# UPCNSL-ABS-PVC-BOT.net
KiCad netlist of a schematic drawn in Altium Designer
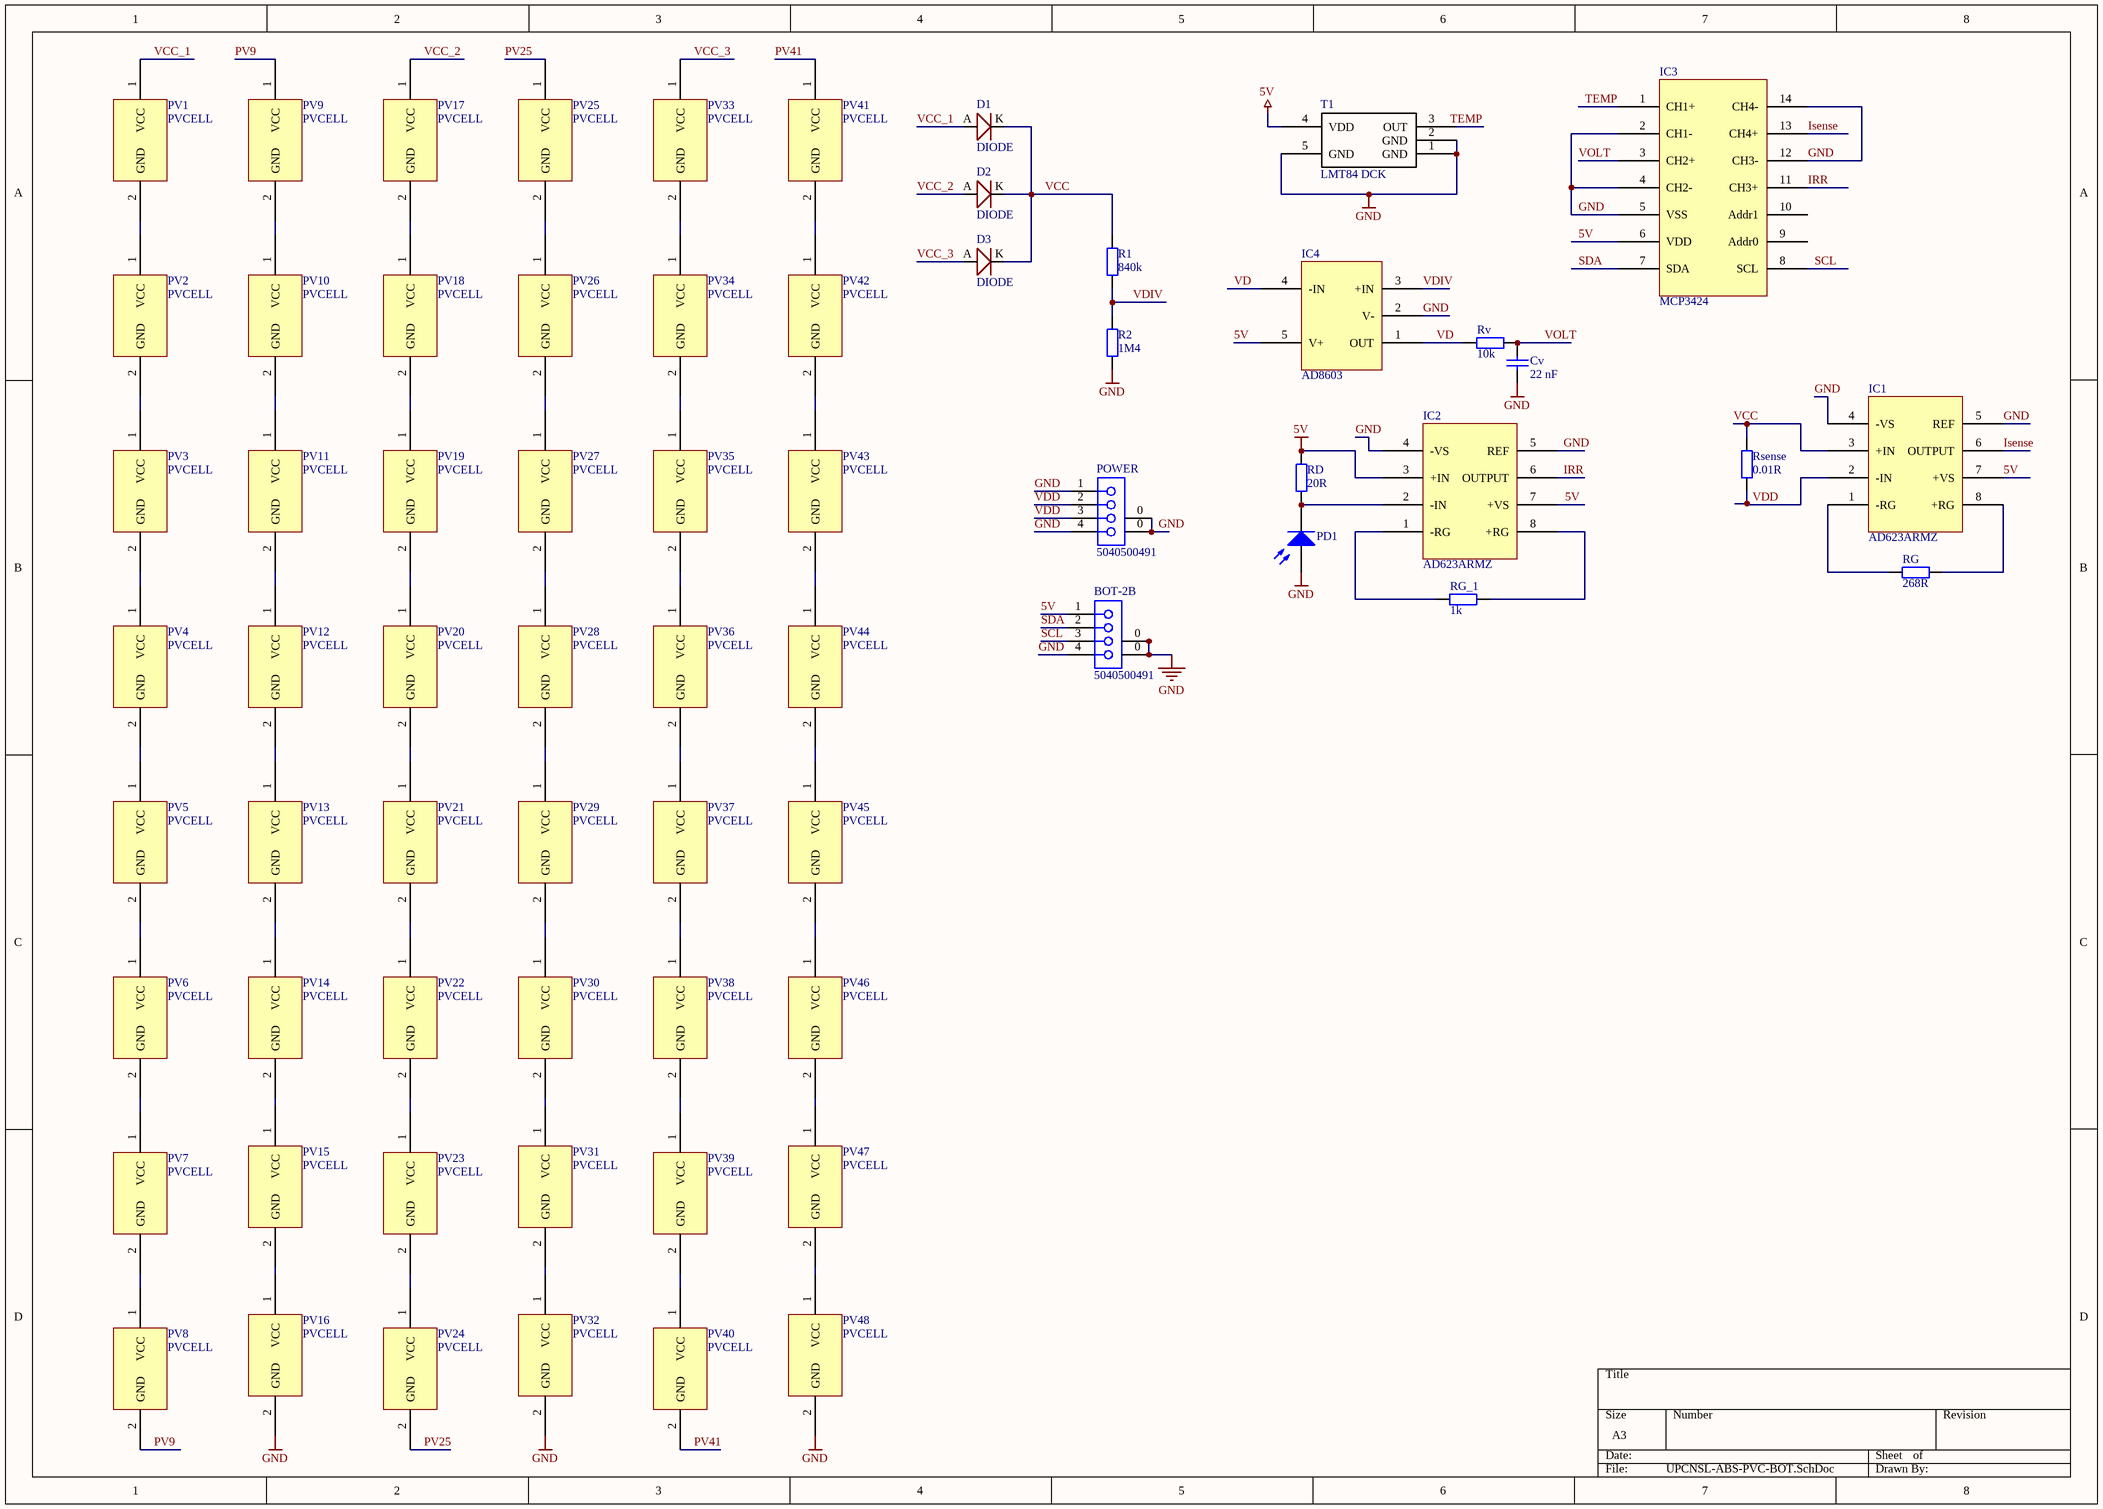
[diagram p0: UPCNSL-ABS-PVC-BOT.SchDoc]

(export (version "E")
  (design (tool "Eeschema 10.0.6"))
  (components
    (comp (ref "BOT-2B")
      (value "5040500491")
      (footprint "5040500491")
      (libsource (lib "3CAT_Connectors") (part "MOLEX_5040500491"))
    )
    (comp (ref "Cv")
      (value "22 nF")
      (footprint "CAP0603")
      (description "Capacitor")
      (fields (field (name "Comment") "CAP0603"))
      (libsource (lib "UPCNSL-ABS-FLS-ARD_v1.2") (part "CAP0603"))
    )
    (comp (ref "D1")
      (value "DIODE")
      (footprint "(Schottky diode) SODFL160X70-2N")
      (libsource (lib "UPCNSL-ABS-FLS-ARD_v1.2") (part "DIODE"))
    )
    (comp (ref "D2")
      (value "DIODE")
      (footprint "(Schottky diode) SODFL160X70-2N")
      (libsource (lib "UPCNSL-ABS-FLS-ARD_v1.2") (part "DIODE"))
    )
    (comp (ref "D3")
      (value "DIODE")
      (footprint "(Schottky diode) SODFL160X70-2N")
      (libsource (lib "UPCNSL-ABS-FLS-ARD_v1.2") (part "DIODE"))
    )
    (comp (ref "IC1")
      (value "AD623ARMZ")
      (footprint "AD623ARMZ")
      (libsource (lib "UPCNSL-ABS-FLS-PVC") (part "AD623ARMZ"))
    )
    (comp (ref "IC2")
      (value "AD623ARMZ")
      (footprint "AD623ARMZ")
      (libsource (lib "UPCNSL-ABS-FLS-PVC") (part "AD623ARMZ"))
    )
    (comp (ref "IC3")
      (value "MCP3424")
      (footprint "MCP3424")
      (description "18-Bit, Multi-Channel ΔΣ Analog-to-Digital Converter with  I2C")
      (libsource (lib "UPCNSL-ABS-FLS-PVC") (part "MCP3424"))
    )
    (comp (ref "IC4")
      (value "AD8603")
      (footprint "AD8603")
      (libsource (lib "UPCNSL-ABS-FLS-PVC") (part "AD8603"))
    )
    (comp (ref "PD1")
      (value "Photo Sen")
      (footprint "C0805")
      (description "Photosensitive Diode")
      (fields (field (name "PUBLISHER") "Altium Limited"))
      (libsource (lib "Miscellaneous Devices") (part "Photo Sen"))
    )
    (comp (ref "POWER")
      (value "5040500491")
      (footprint "5040500491")
      (libsource (lib "3CAT_Connectors") (part "MOLEX_5040500491"))
    )
    (comp (ref "PV1")
      (value "PVCELL")
      (footprint "PV CELLS")
      (description "IXYS KXOB22-12X1L-ND")
      (libsource (lib "UPCNSL-ABS-FLS-PVC") (part "PVCELLS"))
    )
    (comp (ref "PV2")
      (value "PVCELL")
      (footprint "PV CELLS")
      (description "IXYS KXOB22-12X1L-ND")
      (libsource (lib "UPCNSL-ABS-FLS-PVC") (part "PVCELLS"))
    )
    (comp (ref "PV3")
      (value "PVCELL")
      (footprint "PV CELLS")
      (description "IXYS KXOB22-12X1L-ND")
      (libsource (lib "UPCNSL-ABS-FLS-PVC") (part "PVCELLS"))
    )
    (comp (ref "PV4")
      (value "PVCELL")
      (footprint "PV CELLS")
      (description "IXYS KXOB22-12X1L-ND")
      (libsource (lib "UPCNSL-ABS-FLS-PVC") (part "PVCELLS"))
    )
    (comp (ref "PV5")
      (value "PVCELL")
      (footprint "PV CELLS")
      (description "IXYS KXOB22-12X1L-ND")
      (libsource (lib "UPCNSL-ABS-FLS-PVC") (part "PVCELLS"))
    )
    (comp (ref "PV6")
      (value "PVCELL")
      (footprint "PV CELLS")
      (description "IXYS KXOB22-12X1L-ND")
      (libsource (lib "UPCNSL-ABS-FLS-PVC") (part "PVCELLS"))
    )
    (comp (ref "PV7")
      (value "PVCELL")
      (footprint "PV CELLS")
      (description "IXYS KXOB22-12X1L-ND")
      (libsource (lib "UPCNSL-ABS-FLS-PVC") (part "PVCELLS"))
    )
    (comp (ref "PV8")
      (value "PVCELL")
      (footprint "PV CELLS")
      (description "IXYS KXOB22-12X1L-ND")
      (libsource (lib "UPCNSL-ABS-FLS-PVC") (part "PVCELLS"))
    )
    (comp (ref "PV9")
      (value "PVCELL")
      (footprint "PV CELLS")
      (description "IXYS KXOB22-12X1L-ND")
      (libsource (lib "UPCNSL-ABS-FLS-PVC") (part "PVCELLS"))
    )
    (comp (ref "PV10")
      (value "PVCELL")
      (footprint "PV CELLS")
      (description "IXYS KXOB22-12X1L-ND")
      (libsource (lib "UPCNSL-ABS-FLS-PVC") (part "PVCELLS"))
    )
    (comp (ref "PV11")
      (value "PVCELL")
      (footprint "PV CELLS")
      (description "IXYS KXOB22-12X1L-ND")
      (libsource (lib "UPCNSL-ABS-FLS-PVC") (part "PVCELLS"))
    )
    (comp (ref "PV12")
      (value "PVCELL")
      (footprint "PV CELLS")
      (description "IXYS KXOB22-12X1L-ND")
      (libsource (lib "UPCNSL-ABS-FLS-PVC") (part "PVCELLS"))
    )
    (comp (ref "PV13")
      (value "PVCELL")
      (footprint "PV CELLS")
      (description "IXYS KXOB22-12X1L-ND")
      (libsource (lib "UPCNSL-ABS-FLS-PVC") (part "PVCELLS"))
    )
    (comp (ref "PV14")
      (value "PVCELL")
      (footprint "PV CELLS")
      (description "IXYS KXOB22-12X1L-ND")
      (libsource (lib "UPCNSL-ABS-FLS-PVC") (part "PVCELLS"))
    )
    (comp (ref "PV15")
      (value "PVCELL")
      (footprint "PV CELLS")
      (description "IXYS KXOB22-12X1L-ND")
      (libsource (lib "UPCNSL-ABS-FLS-PVC") (part "PVCELLS"))
    )
    (comp (ref "PV16")
      (value "PVCELL")
      (footprint "PV CELLS")
      (description "IXYS KXOB22-12X1L-ND")
      (libsource (lib "UPCNSL-ABS-FLS-PVC") (part "PVCELLS"))
    )
    (comp (ref "PV17")
      (value "PVCELL")
      (footprint "PV CELLS")
      (description "IXYS KXOB22-12X1L-ND")
      (libsource (lib "UPCNSL-ABS-FLS-PVC") (part "PVCELLS"))
    )
    (comp (ref "PV18")
      (value "PVCELL")
      (footprint "PV CELLS")
      (description "IXYS KXOB22-12X1L-ND")
      (libsource (lib "UPCNSL-ABS-FLS-PVC") (part "PVCELLS"))
    )
    (comp (ref "PV19")
      (value "PVCELL")
      (footprint "PV CELLS")
      (description "IXYS KXOB22-12X1L-ND")
      (libsource (lib "UPCNSL-ABS-FLS-PVC") (part "PVCELLS"))
    )
    (comp (ref "PV20")
      (value "PVCELL")
      (footprint "PV CELLS")
      (description "IXYS KXOB22-12X1L-ND")
      (libsource (lib "UPCNSL-ABS-FLS-PVC") (part "PVCELLS"))
    )
    (comp (ref "PV21")
      (value "PVCELL")
      (footprint "PV CELLS")
      (description "IXYS KXOB22-12X1L-ND")
      (libsource (lib "UPCNSL-ABS-FLS-PVC") (part "PVCELLS"))
    )
    (comp (ref "PV22")
      (value "PVCELL")
      (footprint "PV CELLS")
      (description "IXYS KXOB22-12X1L-ND")
      (libsource (lib "UPCNSL-ABS-FLS-PVC") (part "PVCELLS"))
    )
    (comp (ref "PV23")
      (value "PVCELL")
      (footprint "PV CELLS")
      (description "IXYS KXOB22-12X1L-ND")
      (libsource (lib "UPCNSL-ABS-FLS-PVC") (part "PVCELLS"))
    )
    (comp (ref "PV24")
      (value "PVCELL")
      (footprint "PV CELLS")
      (description "IXYS KXOB22-12X1L-ND")
      (libsource (lib "UPCNSL-ABS-FLS-PVC") (part "PVCELLS"))
    )
    (comp (ref "PV25")
      (value "PVCELL")
      (footprint "PV CELLS")
      (description "IXYS KXOB22-12X1L-ND")
      (libsource (lib "UPCNSL-ABS-FLS-PVC") (part "PVCELLS"))
    )
    (comp (ref "PV26")
      (value "PVCELL")
      (footprint "PV CELLS")
      (description "IXYS KXOB22-12X1L-ND")
      (libsource (lib "UPCNSL-ABS-FLS-PVC") (part "PVCELLS"))
    )
    (comp (ref "PV27")
      (value "PVCELL")
      (footprint "PV CELLS")
      (description "IXYS KXOB22-12X1L-ND")
      (libsource (lib "UPCNSL-ABS-FLS-PVC") (part "PVCELLS"))
    )
    (comp (ref "PV28")
      (value "PVCELL")
      (footprint "PV CELLS")
      (description "IXYS KXOB22-12X1L-ND")
      (libsource (lib "UPCNSL-ABS-FLS-PVC") (part "PVCELLS"))
    )
    (comp (ref "PV29")
      (value "PVCELL")
      (footprint "PV CELLS")
      (description "IXYS KXOB22-12X1L-ND")
      (libsource (lib "UPCNSL-ABS-FLS-PVC") (part "PVCELLS"))
    )
    (comp (ref "PV30")
      (value "PVCELL")
      (footprint "PV CELLS")
      (description "IXYS KXOB22-12X1L-ND")
      (libsource (lib "UPCNSL-ABS-FLS-PVC") (part "PVCELLS"))
    )
    (comp (ref "PV31")
      (value "PVCELL")
      (footprint "PV CELLS")
      (description "IXYS KXOB22-12X1L-ND")
      (libsource (lib "UPCNSL-ABS-FLS-PVC") (part "PVCELLS"))
    )
    (comp (ref "PV32")
      (value "PVCELL")
      (footprint "PV CELLS")
      (description "IXYS KXOB22-12X1L-ND")
      (libsource (lib "UPCNSL-ABS-FLS-PVC") (part "PVCELLS"))
    )
    (comp (ref "PV33")
      (value "PVCELL")
      (footprint "PV CELLS")
      (description "IXYS KXOB22-12X1L-ND")
      (libsource (lib "UPCNSL-ABS-FLS-PVC") (part "PVCELLS"))
    )
    (comp (ref "PV34")
      (value "PVCELL")
      (footprint "PV CELLS")
      (description "IXYS KXOB22-12X1L-ND")
      (libsource (lib "UPCNSL-ABS-FLS-PVC") (part "PVCELLS"))
    )
    (comp (ref "PV35")
      (value "PVCELL")
      (footprint "PV CELLS")
      (description "IXYS KXOB22-12X1L-ND")
      (libsource (lib "UPCNSL-ABS-FLS-PVC") (part "PVCELLS"))
    )
    (comp (ref "PV36")
      (value "PVCELL")
      (footprint "PV CELLS")
      (description "IXYS KXOB22-12X1L-ND")
      (libsource (lib "UPCNSL-ABS-FLS-PVC") (part "PVCELLS"))
    )
    (comp (ref "PV37")
      (value "PVCELL")
      (footprint "PV CELLS")
      (description "IXYS KXOB22-12X1L-ND")
      (libsource (lib "UPCNSL-ABS-FLS-PVC") (part "PVCELLS"))
    )
    (comp (ref "PV38")
      (value "PVCELL")
      (footprint "PV CELLS")
      (description "IXYS KXOB22-12X1L-ND")
      (libsource (lib "UPCNSL-ABS-FLS-PVC") (part "PVCELLS"))
    )
    (comp (ref "PV39")
      (value "PVCELL")
      (footprint "PV CELLS")
      (description "IXYS KXOB22-12X1L-ND")
      (libsource (lib "UPCNSL-ABS-FLS-PVC") (part "PVCELLS"))
    )
    (comp (ref "PV40")
      (value "PVCELL")
      (footprint "PV CELLS")
      (description "IXYS KXOB22-12X1L-ND")
      (libsource (lib "UPCNSL-ABS-FLS-PVC") (part "PVCELLS"))
    )
    (comp (ref "PV41")
      (value "PVCELL")
      (footprint "PV CELLS")
      (description "IXYS KXOB22-12X1L-ND")
      (libsource (lib "UPCNSL-ABS-FLS-PVC") (part "PVCELLS"))
    )
    (comp (ref "PV42")
      (value "PVCELL")
      (footprint "PV CELLS")
      (description "IXYS KXOB22-12X1L-ND")
      (libsource (lib "UPCNSL-ABS-FLS-PVC") (part "PVCELLS"))
    )
    (comp (ref "PV43")
      (value "PVCELL")
      (footprint "PV CELLS")
      (description "IXYS KXOB22-12X1L-ND")
      (libsource (lib "UPCNSL-ABS-FLS-PVC") (part "PVCELLS"))
    )
    (comp (ref "PV44")
      (value "PVCELL")
      (footprint "PV CELLS")
      (description "IXYS KXOB22-12X1L-ND")
      (libsource (lib "UPCNSL-ABS-FLS-PVC") (part "PVCELLS"))
    )
    (comp (ref "PV45")
      (value "PVCELL")
      (footprint "PV CELLS")
      (description "IXYS KXOB22-12X1L-ND")
      (libsource (lib "UPCNSL-ABS-FLS-PVC") (part "PVCELLS"))
    )
    (comp (ref "PV46")
      (value "PVCELL")
      (footprint "PV CELLS")
      (description "IXYS KXOB22-12X1L-ND")
      (libsource (lib "UPCNSL-ABS-FLS-PVC") (part "PVCELLS"))
    )
    (comp (ref "PV47")
      (value "PVCELL")
      (footprint "PV CELLS")
      (description "IXYS KXOB22-12X1L-ND")
      (libsource (lib "UPCNSL-ABS-FLS-PVC") (part "PVCELLS"))
    )
    (comp (ref "PV48")
      (value "PVCELL")
      (footprint "PV CELLS")
      (description "IXYS KXOB22-12X1L-ND")
      (libsource (lib "UPCNSL-ABS-FLS-PVC") (part "PVCELLS"))
    )
    (comp (ref "R1")
      (value "840k")
      (footprint "RES0603")
      (description "Resistor")
      (fields (field (name "Comment") "RES0603"))
      (libsource (lib "") (part "RES0603_1"))
    )
    (comp (ref "R2")
      (value "1M4")
      (footprint "RES0603")
      (description "Resistor")
      (fields (field (name "Comment") "RES0603"))
      (libsource (lib "") (part "RES0603_1"))
    )
    (comp (ref "RD")
      (value "20R")
      (footprint "RES0603")
      (description "Resistor")
      (fields (field (name "Comment") "RES0603"))
      (libsource (lib "") (part "RES0603_1"))
    )
    (comp (ref "RG")
      (value "268R")
      (footprint "RES0603")
      (description "Resistor")
      (fields (field (name "Comment") "RES0603"))
      (libsource (lib "UPCNSL-ABS-FLS-ARD_v1.2") (part "RES0603"))
    )
    (comp (ref "RG_1")
      (value "1k")
      (footprint "RES0603")
      (description "Resistor")
      (fields (field (name "Comment") "RES0603"))
      (libsource (lib "UPCNSL-ABS-FLS-ARD_v1.2") (part "RES0603"))
    )
    (comp (ref "Rsense")
      (value "0.01R")
      (footprint "RES0603")
      (description "Resistor")
      (fields (field (name "Comment") "RES0603"))
      (libsource (lib "") (part "RES0603_1"))
    )
    (comp (ref "Rv")
      (value "10k")
      (footprint "RES0603")
      (description "Resistor")
      (fields (field (name "Comment") "RES0603"))
      (libsource (lib "UPCNSL-ABS-FLS-ARD_v1.2") (part "RES0603"))
    )
    (comp (ref "T1")
      (value "LMT84 DCK")
      (footprint "DCK/SOT65P210X110-5N")
      (libsource (lib "UPCNSL-ABS-FLS-PVC") (part "LMT84 DCK"))
    )
  )
  (nets
    (net (code "1") (name "/IRR") (class "Default")
      (node (ref "IC2") (pin "6") (pinfunction "OUTPUT_6") (pintype "passive"))
      (node (ref "IC3") (pin "11") (pinfunction "CH3+_11") (pintype "passive"))
    )
    (net (code "2") (name "/Isense") (class "Default")
      (node (ref "IC1") (pin "6") (pinfunction "OUTPUT_6") (pintype "passive"))
      (node (ref "IC3") (pin "13") (pinfunction "CH4+_13") (pintype "passive"))
    )
    (net (code "3") (name "/PV9") (class "Default")
      (node (ref "PV8") (pin "2") (pinfunction "GND_2") (pintype "passive"))
      (node (ref "PV9") (pin "1") (pinfunction "VCC_1") (pintype "passive"))
    )
    (net (code "4") (name "/PV25") (class "Default")
      (node (ref "PV24") (pin "2") (pinfunction "GND_2") (pintype "passive"))
      (node (ref "PV25") (pin "1") (pinfunction "VCC_1") (pintype "passive"))
    )
    (net (code "5") (name "/PV41") (class "Default")
      (node (ref "PV40") (pin "2") (pinfunction "GND_2") (pintype "passive"))
      (node (ref "PV41") (pin "1") (pinfunction "VCC_1") (pintype "passive"))
    )
    (net (code "6") (name "/SCL") (class "Default")
      (node (ref "BOT-2B") (pin "3") (pinfunction "3_3") (pintype "passive"))
      (node (ref "IC3") (pin "8") (pinfunction "SCL_8") (pintype "passive"))
    )
    (net (code "7") (name "/SDA") (class "Default")
      (node (ref "BOT-2B") (pin "2") (pinfunction "2_2") (pintype "passive"))
      (node (ref "IC3") (pin "7") (pinfunction "SDA_7") (pintype "passive"))
    )
    (net (code "8") (name "/TEMP") (class "Default")
      (node (ref "IC3") (pin "1") (pinfunction "CH1+_1") (pintype "passive"))
    )
    (net (code "9") (name "/VCC") (class "Default")
      (node (ref "D1") (pin "K") (pinfunction "K_K") (pintype "passive"))
      (node (ref "D2") (pin "K") (pinfunction "K_K") (pintype "passive"))
      (node (ref "D3") (pin "K") (pinfunction "K_K") (pintype "passive"))
      (node (ref "IC1") (pin "3") (pinfunction "+IN_3") (pintype "passive"))
      (node (ref "R1") (pin "2") (pinfunction "2_2") (pintype "passive"))
      (node (ref "Rsense") (pin "2") (pinfunction "2_2") (pintype "passive"))
    )
    (net (code "10") (name "/VCC_1") (class "Default")
      (node (ref "D1") (pin "A") (pinfunction "A_A") (pintype "passive"))
      (node (ref "PV1") (pin "1") (pinfunction "VCC_1") (pintype "passive"))
    )
    (net (code "11") (name "/VCC_2") (class "Default")
      (node (ref "D2") (pin "A") (pinfunction "A_A") (pintype "passive"))
      (node (ref "PV17") (pin "1") (pinfunction "VCC_1") (pintype "passive"))
    )
    (net (code "12") (name "/VCC_3") (class "Default")
      (node (ref "D3") (pin "A") (pinfunction "A_A") (pintype "passive"))
      (node (ref "PV33") (pin "1") (pinfunction "VCC_1") (pintype "passive"))
    )
    (net (code "13") (name "/VD") (class "Default")
      (node (ref "IC4") (pin "1") (pinfunction "OUT_1") (pintype "passive"))
      (node (ref "IC4") (pin "4") (pinfunction "-IN_4") (pintype "passive"))
      (node (ref "Rv") (pin "1") (pinfunction "1_1") (pintype "passive"))
    )
    (net (code "14") (name "/VDD") (class "Default")
      (node (ref "IC1") (pin "2") (pinfunction "-IN_2") (pintype "passive"))
      (node (ref "POWER") (pin "2") (pinfunction "2_2") (pintype "passive"))
      (node (ref "POWER") (pin "3") (pinfunction "3_3") (pintype "passive"))
      (node (ref "Rsense") (pin "1") (pinfunction "1_1") (pintype "passive"))
    )
    (net (code "15") (name "/VDIV") (class "Default")
      (node (ref "IC4") (pin "3") (pinfunction "+IN_3") (pintype "passive"))
      (node (ref "R1") (pin "1") (pinfunction "1_1") (pintype "passive"))
      (node (ref "R2") (pin "2") (pinfunction "2_2") (pintype "passive"))
    )
    (net (code "16") (name "/VOLT") (class "Default")
      (node (ref "Cv") (pin "2") (pinfunction "2_2") (pintype "passive"))
      (node (ref "IC3") (pin "3") (pinfunction "CH2+_3") (pintype "passive"))
      (node (ref "Rv") (pin "2") (pinfunction "2_2") (pintype "passive"))
    )
    (net (code "17") (name "5V") (class "Default")
      (node (ref "BOT-2B") (pin "1") (pinfunction "1_1") (pintype "passive"))
      (node (ref "IC1") (pin "7") (pinfunction "+VS_7") (pintype "passive"))
      (node (ref "IC2") (pin "3") (pinfunction "+IN_3") (pintype "passive"))
      (node (ref "IC2") (pin "7") (pinfunction "+VS_7") (pintype "passive"))
      (node (ref "IC3") (pin "6") (pinfunction "VDD_6") (pintype "passive"))
      (node (ref "IC4") (pin "5") (pinfunction "V+_5") (pintype "passive"))
      (node (ref "RD") (pin "2") (pinfunction "2_2") (pintype "passive"))
      (node (ref "T1") (pin "4") (pinfunction "VDD_4") (pintype "passive"))
    )
    (net (code "18") (name "GND") (class "Default")
      (node (ref "BOT-2B") (pin "0") (pinfunction "MH1_0") (pintype "passive"))
      (node (ref "BOT-2B") (pin "4") (pinfunction "4_4") (pintype "passive"))
      (node (ref "Cv") (pin "1") (pinfunction "1_1") (pintype "passive"))
      (node (ref "IC1") (pin "4") (pinfunction "-VS_4") (pintype "passive"))
      (node (ref "IC1") (pin "5") (pinfunction "REF_5") (pintype "passive"))
      (node (ref "IC2") (pin "4") (pinfunction "-VS_4") (pintype "passive"))
      (node (ref "IC2") (pin "5") (pinfunction "REF_5") (pintype "passive"))
      (node (ref "IC3") (pin "12") (pinfunction "CH3-_12") (pintype "passive"))
      (node (ref "IC3") (pin "14") (pinfunction "CH4-_14") (pintype "passive"))
      (node (ref "IC3") (pin "2") (pinfunction "CH1-_2") (pintype "passive"))
      (node (ref "IC3") (pin "4") (pinfunction "CH2-_4") (pintype "passive"))
      (node (ref "IC3") (pin "5") (pinfunction "VSS_5") (pintype "passive"))
      (node (ref "IC4") (pin "2") (pinfunction "V-_2") (pintype "passive"))
      (node (ref "PD1") (pin "1") (pinfunction "A_1") (pintype "passive"))
      (node (ref "POWER") (pin "0") (pinfunction "MH1_0") (pintype "passive"))
      (node (ref "POWER") (pin "1") (pinfunction "1_1") (pintype "passive"))
      (node (ref "POWER") (pin "4") (pinfunction "4_4") (pintype "passive"))
      (node (ref "PV16") (pin "2") (pinfunction "GND_2") (pintype "passive"))
      (node (ref "PV32") (pin "2") (pinfunction "GND_2") (pintype "passive"))
      (node (ref "PV48") (pin "2") (pinfunction "GND_2") (pintype "passive"))
      (node (ref "R2") (pin "1") (pinfunction "1_1") (pintype "passive"))
      (node (ref "T1") (pin "1") (pinfunction "GND_1") (pintype "passive"))
      (node (ref "T1") (pin "2") (pinfunction "GND_2") (pintype "passive"))
      (node (ref "T1") (pin "5") (pinfunction "GND_5") (pintype "passive"))
    )
    (net (code "19") (name "Net-(IC1-+RG)") (class "Default")
      (node (ref "IC1") (pin "8") (pinfunction "+RG_8") (pintype "passive"))
      (node (ref "RG") (pin "2") (pinfunction "2_2") (pintype "passive"))
    )
    (net (code "20") (name "Net-(IC1--RG)") (class "Default")
      (node (ref "IC1") (pin "1") (pinfunction "-RG_1") (pintype "passive"))
      (node (ref "RG") (pin "1") (pinfunction "1_1") (pintype "passive"))
    )
    (net (code "21") (name "Net-(IC2-+RG)") (class "Default")
      (node (ref "IC2") (pin "8") (pinfunction "+RG_8") (pintype "passive"))
      (node (ref "RG_1") (pin "2") (pinfunction "2_2") (pintype "passive"))
    )
    (net (code "22") (name "Net-(IC2--IN)") (class "Default")
      (node (ref "IC2") (pin "2") (pinfunction "-IN_2") (pintype "passive"))
      (node (ref "PD1") (pin "2") (pinfunction "K_2") (pintype "passive"))
      (node (ref "RD") (pin "1") (pinfunction "1_1") (pintype "passive"))
    )
    (net (code "23") (name "Net-(IC2--RG)") (class "Default")
      (node (ref "IC2") (pin "1") (pinfunction "-RG_1") (pintype "passive"))
      (node (ref "RG_1") (pin "1") (pinfunction "1_1") (pintype "passive"))
    )
    (net (code "24") (name "Net-(PV1-GND)") (class "Default")
      (node (ref "PV1") (pin "2") (pinfunction "GND_2") (pintype "passive"))
      (node (ref "PV2") (pin "1") (pinfunction "VCC_1") (pintype "passive"))
    )
    (net (code "25") (name "Net-(PV2-GND)") (class "Default")
      (node (ref "PV2") (pin "2") (pinfunction "GND_2") (pintype "passive"))
      (node (ref "PV3") (pin "1") (pinfunction "VCC_1") (pintype "passive"))
    )
    (net (code "26") (name "Net-(PV3-GND)") (class "Default")
      (node (ref "PV3") (pin "2") (pinfunction "GND_2") (pintype "passive"))
      (node (ref "PV4") (pin "1") (pinfunction "VCC_1") (pintype "passive"))
    )
    (net (code "27") (name "Net-(PV4-GND)") (class "Default")
      (node (ref "PV4") (pin "2") (pinfunction "GND_2") (pintype "passive"))
      (node (ref "PV5") (pin "1") (pinfunction "VCC_1") (pintype "passive"))
    )
    (net (code "28") (name "Net-(PV5-GND)") (class "Default")
      (node (ref "PV5") (pin "2") (pinfunction "GND_2") (pintype "passive"))
      (node (ref "PV6") (pin "1") (pinfunction "VCC_1") (pintype "passive"))
    )
    (net (code "29") (name "Net-(PV6-GND)") (class "Default")
      (node (ref "PV6") (pin "2") (pinfunction "GND_2") (pintype "passive"))
      (node (ref "PV7") (pin "1") (pinfunction "VCC_1") (pintype "passive"))
    )
    (net (code "30") (name "Net-(PV7-GND)") (class "Default")
      (node (ref "PV7") (pin "2") (pinfunction "GND_2") (pintype "passive"))
      (node (ref "PV8") (pin "1") (pinfunction "VCC_1") (pintype "passive"))
    )
    (net (code "31") (name "Net-(PV10-GND)") (class "Default")
      (node (ref "PV10") (pin "2") (pinfunction "GND_2") (pintype "passive"))
      (node (ref "PV11") (pin "1") (pinfunction "VCC_1") (pintype "passive"))
    )
    (net (code "32") (name "Net-(PV10-VCC)") (class "Default")
      (node (ref "PV10") (pin "1") (pinfunction "VCC_1") (pintype "passive"))
      (node (ref "PV9") (pin "2") (pinfunction "GND_2") (pintype "passive"))
    )
    (net (code "33") (name "Net-(PV11-GND)") (class "Default")
      (node (ref "PV11") (pin "2") (pinfunction "GND_2") (pintype "passive"))
      (node (ref "PV12") (pin "1") (pinfunction "VCC_1") (pintype "passive"))
    )
    (net (code "34") (name "Net-(PV12-GND)") (class "Default")
      (node (ref "PV12") (pin "2") (pinfunction "GND_2") (pintype "passive"))
      (node (ref "PV13") (pin "1") (pinfunction "VCC_1") (pintype "passive"))
    )
    (net (code "35") (name "Net-(PV13-GND)") (class "Default")
      (node (ref "PV13") (pin "2") (pinfunction "GND_2") (pintype "passive"))
      (node (ref "PV14") (pin "1") (pinfunction "VCC_1") (pintype "passive"))
    )
    (net (code "36") (name "Net-(PV14-GND)") (class "Default")
      (node (ref "PV14") (pin "2") (pinfunction "GND_2") (pintype "passive"))
      (node (ref "PV15") (pin "1") (pinfunction "VCC_1") (pintype "passive"))
    )
    (net (code "37") (name "Net-(PV15-GND)") (class "Default")
      (node (ref "PV15") (pin "2") (pinfunction "GND_2") (pintype "passive"))
      (node (ref "PV16") (pin "1") (pinfunction "VCC_1") (pintype "passive"))
    )
    (net (code "38") (name "Net-(PV17-GND)") (class "Default")
      (node (ref "PV17") (pin "2") (pinfunction "GND_2") (pintype "passive"))
      (node (ref "PV18") (pin "1") (pinfunction "VCC_1") (pintype "passive"))
    )
    (net (code "39") (name "Net-(PV18-GND)") (class "Default")
      (node (ref "PV18") (pin "2") (pinfunction "GND_2") (pintype "passive"))
      (node (ref "PV19") (pin "1") (pinfunction "VCC_1") (pintype "passive"))
    )
    (net (code "40") (name "Net-(PV19-GND)") (class "Default")
      (node (ref "PV19") (pin "2") (pinfunction "GND_2") (pintype "passive"))
      (node (ref "PV20") (pin "1") (pinfunction "VCC_1") (pintype "passive"))
    )
    (net (code "41") (name "Net-(PV20-GND)") (class "Default")
      (node (ref "PV20") (pin "2") (pinfunction "GND_2") (pintype "passive"))
      (node (ref "PV21") (pin "1") (pinfunction "VCC_1") (pintype "passive"))
    )
    (net (code "42") (name "Net-(PV21-GND)") (class "Default")
      (node (ref "PV21") (pin "2") (pinfunction "GND_2") (pintype "passive"))
      (node (ref "PV22") (pin "1") (pinfunction "VCC_1") (pintype "passive"))
    )
    (net (code "43") (name "Net-(PV22-GND)") (class "Default")
      (node (ref "PV22") (pin "2") (pinfunction "GND_2") (pintype "passive"))
      (node (ref "PV23") (pin "1") (pinfunction "VCC_1") (pintype "passive"))
    )
    (net (code "44") (name "Net-(PV23-GND)") (class "Default")
      (node (ref "PV23") (pin "2") (pinfunction "GND_2") (pintype "passive"))
      (node (ref "PV24") (pin "1") (pinfunction "VCC_1") (pintype "passive"))
    )
    (net (code "45") (name "Net-(PV25-GND)") (class "Default")
      (node (ref "PV25") (pin "2") (pinfunction "GND_2") (pintype "passive"))
      (node (ref "PV26") (pin "1") (pinfunction "VCC_1") (pintype "passive"))
    )
    (net (code "46") (name "Net-(PV26-GND)") (class "Default")
      (node (ref "PV26") (pin "2") (pinfunction "GND_2") (pintype "passive"))
      (node (ref "PV27") (pin "1") (pinfunction "VCC_1") (pintype "passive"))
    )
    (net (code "47") (name "Net-(PV27-GND)") (class "Default")
      (node (ref "PV27") (pin "2") (pinfunction "GND_2") (pintype "passive"))
      (node (ref "PV28") (pin "1") (pinfunction "VCC_1") (pintype "passive"))
    )
    (net (code "48") (name "Net-(PV28-GND)") (class "Default")
      (node (ref "PV28") (pin "2") (pinfunction "GND_2") (pintype "passive"))
      (node (ref "PV29") (pin "1") (pinfunction "VCC_1") (pintype "passive"))
    )
    (net (code "49") (name "Net-(PV29-GND)") (class "Default")
      (node (ref "PV29") (pin "2") (pinfunction "GND_2") (pintype "passive"))
      (node (ref "PV30") (pin "1") (pinfunction "VCC_1") (pintype "passive"))
    )
    (net (code "50") (name "Net-(PV30-GND)") (class "Default")
      (node (ref "PV30") (pin "2") (pinfunction "GND_2") (pintype "passive"))
      (node (ref "PV31") (pin "1") (pinfunction "VCC_1") (pintype "passive"))
    )
    (net (code "51") (name "Net-(PV31-GND)") (class "Default")
      (node (ref "PV31") (pin "2") (pinfunction "GND_2") (pintype "passive"))
      (node (ref "PV32") (pin "1") (pinfunction "VCC_1") (pintype "passive"))
    )
    (net (code "52") (name "Net-(PV33-GND)") (class "Default")
      (node (ref "PV33") (pin "2") (pinfunction "GND_2") (pintype "passive"))
      (node (ref "PV34") (pin "1") (pinfunction "VCC_1") (pintype "passive"))
    )
    (net (code "53") (name "Net-(PV34-GND)") (class "Default")
      (node (ref "PV34") (pin "2") (pinfunction "GND_2") (pintype "passive"))
      (node (ref "PV35") (pin "1") (pinfunction "VCC_1") (pintype "passive"))
    )
    (net (code "54") (name "Net-(PV35-GND)") (class "Default")
      (node (ref "PV35") (pin "2") (pinfunction "GND_2") (pintype "passive"))
      (node (ref "PV36") (pin "1") (pinfunction "VCC_1") (pintype "passive"))
    )
    (net (code "55") (name "Net-(PV36-GND)") (class "Default")
      (node (ref "PV36") (pin "2") (pinfunction "GND_2") (pintype "passive"))
      (node (ref "PV37") (pin "1") (pinfunction "VCC_1") (pintype "passive"))
    )
    (net (code "56") (name "Net-(PV37-GND)") (class "Default")
      (node (ref "PV37") (pin "2") (pinfunction "GND_2") (pintype "passive"))
      (node (ref "PV38") (pin "1") (pinfunction "VCC_1") (pintype "passive"))
    )
    (net (code "57") (name "Net-(PV38-GND)") (class "Default")
      (node (ref "PV38") (pin "2") (pinfunction "GND_2") (pintype "passive"))
      (node (ref "PV39") (pin "1") (pinfunction "VCC_1") (pintype "passive"))
    )
    (net (code "58") (name "Net-(PV39-GND)") (class "Default")
      (node (ref "PV39") (pin "2") (pinfunction "GND_2") (pintype "passive"))
      (node (ref "PV40") (pin "1") (pinfunction "VCC_1") (pintype "passive"))
    )
    (net (code "59") (name "Net-(PV41-GND)") (class "Default")
      (node (ref "PV41") (pin "2") (pinfunction "GND_2") (pintype "passive"))
      (node (ref "PV42") (pin "1") (pinfunction "VCC_1") (pintype "passive"))
    )
    (net (code "60") (name "Net-(PV42-GND)") (class "Default")
      (node (ref "PV42") (pin "2") (pinfunction "GND_2") (pintype "passive"))
      (node (ref "PV43") (pin "1") (pinfunction "VCC_1") (pintype "passive"))
    )
    (net (code "61") (name "Net-(PV43-GND)") (class "Default")
      (node (ref "PV43") (pin "2") (pinfunction "GND_2") (pintype "passive"))
      (node (ref "PV44") (pin "1") (pinfunction "VCC_1") (pintype "passive"))
    )
    (net (code "62") (name "Net-(PV44-GND)") (class "Default")
      (node (ref "PV44") (pin "2") (pinfunction "GND_2") (pintype "passive"))
      (node (ref "PV45") (pin "1") (pinfunction "VCC_1") (pintype "passive"))
    )
    (net (code "63") (name "Net-(PV45-GND)") (class "Default")
      (node (ref "PV45") (pin "2") (pinfunction "GND_2") (pintype "passive"))
      (node (ref "PV46") (pin "1") (pinfunction "VCC_1") (pintype "passive"))
    )
    (net (code "64") (name "Net-(PV46-GND)") (class "Default")
      (node (ref "PV46") (pin "2") (pinfunction "GND_2") (pintype "passive"))
      (node (ref "PV47") (pin "1") (pinfunction "VCC_1") (pintype "passive"))
    )
    (net (code "65") (name "Net-(PV47-GND)") (class "Default")
      (node (ref "PV47") (pin "2") (pinfunction "GND_2") (pintype "passive"))
      (node (ref "PV48") (pin "1") (pinfunction "VCC_1") (pintype "passive"))
    )
    (net (code "66") (name "unconnected-(IC3-Addr0-Pad9)") (class "Default")
      (node (ref "IC3") (pin "9") (pinfunction "Addr0_9") (pintype "passive"))
    )
    (net (code "67") (name "unconnected-(IC3-Addr1-Pad10)") (class "Default")
      (node (ref "IC3") (pin "10") (pinfunction "Addr1_10") (pintype "passive"))
    )
    (net (code "68") (name "unconnected-(T1-OUT-Pad3)") (class "Default")
      (node (ref "T1") (pin "3") (pinfunction "OUT_3") (pintype "passive"))
    )
  )
)
